# power_PROTECTION.net
KiCad netlist of a schematic drawn in Altium Designer
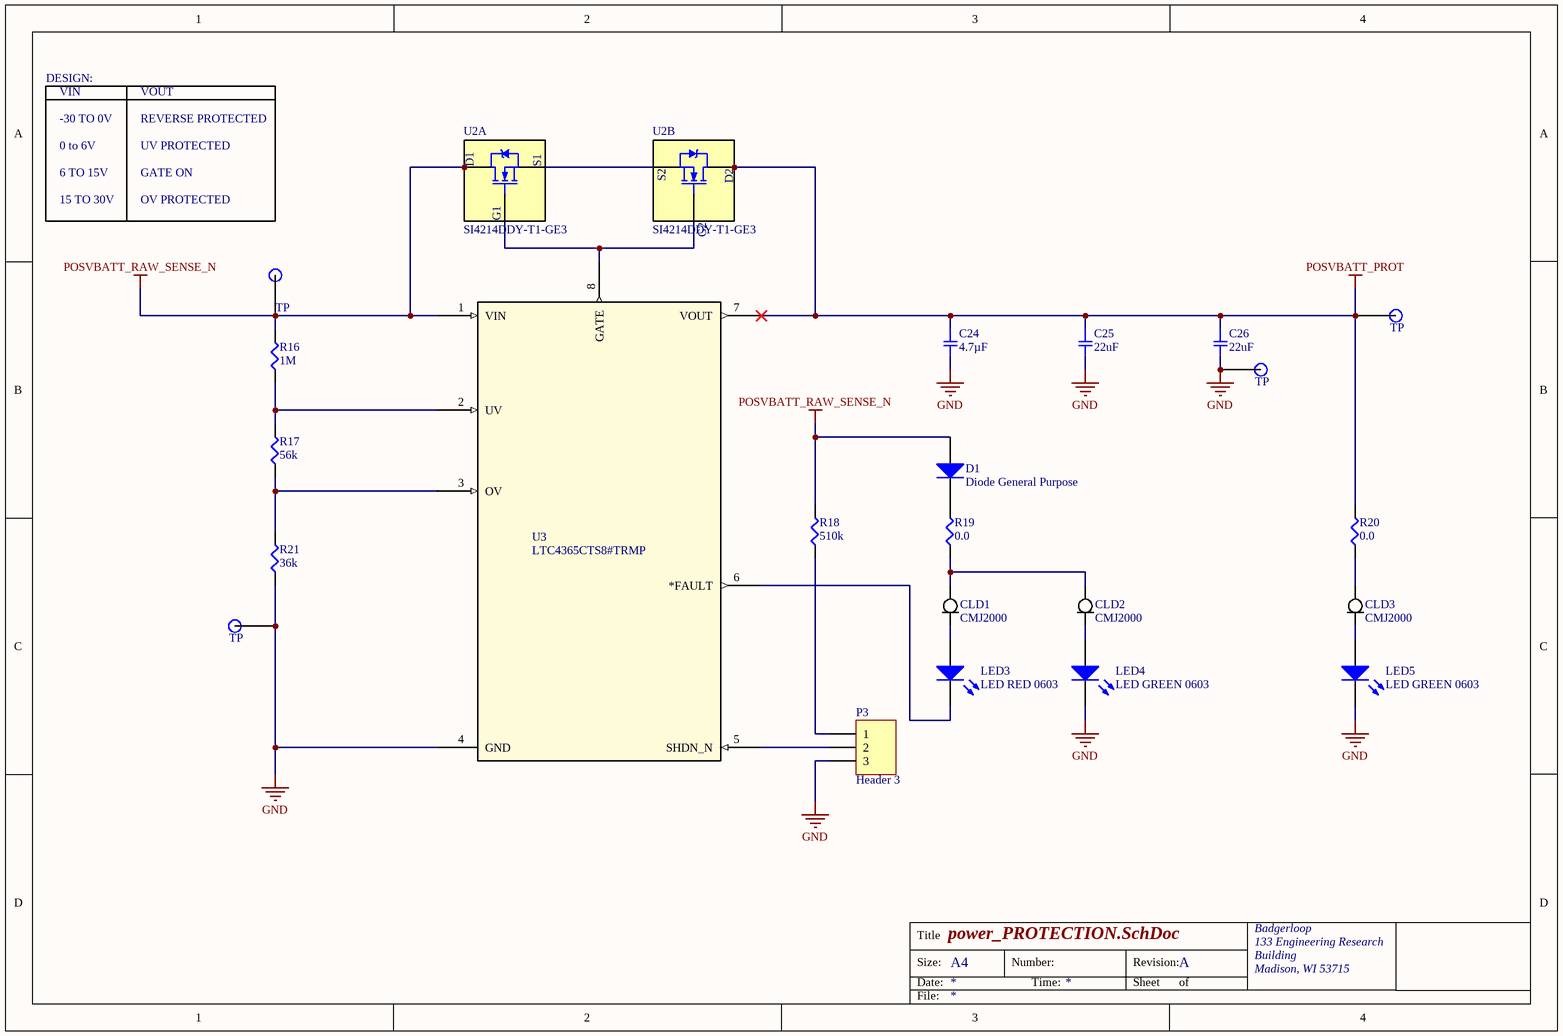
[diagram p0: power_PROTECTION.SchDoc]

(export (version "E")
  (design (tool "Eeschema 10.0.6"))
  (components
    (comp (ref "C24")
      (value "4.7µF")
      (footprint "SMD-0805C")
      (description "CAP CER 4.7UF 50V X5R 0805")
      (fields
        (field (name "DIGI-KEY PART NUMBER") "490-10751-1-ND")
        (field (name "PART NUMBER") "GRM21BR61H475KE51L")
      )
      (libsource (lib "capacitor") (part "GRM21BR61H475KE51L"))
    )
    (comp (ref "C25")
      (value "22uF")
      (footprint "SMD-0805C")
      (description "CAP CER 10000PF 250V X7T 0805")
      (fields
        (field (name "DIGI-KEY PART NUMBER") "445-11527-1-ND")
        (field (name "PART NUMBER") "C2012JB1V226M125AC")
      )
      (libsource (lib "capacitor") (part "GC321AD72E103KX01D"))
    )
    (comp (ref "C26")
      (value "22uF")
      (footprint "SMD-0805C")
      (description "CAP CER 10000PF 250V X7T 0805")
      (fields
        (field (name "DIGI-KEY PART NUMBER") "445-11527-1-ND")
        (field (name "PART NUMBER") "C2012JB1V226M125AC")
      )
      (libsource (lib "capacitor") (part "GC321AD72E103KX01D"))
    )
    (comp (ref "CLD1")
      (value "CMJ2000")
      (footprint "SODFL350X80-2N")
      (description "DIODE CURRENT LIMITING SINGLE SM")
      (fields (field (name "MANUFACTURER") "Central Semiconductor Corp"))
      (libsource (lib "misc") (part "DIODE Current Limiting Single SM"))
    )
    (comp (ref "CLD2")
      (value "CMJ2000")
      (footprint "SODFL350X80-2N")
      (description "DIODE CURRENT LIMITING SINGLE SM")
      (fields (field (name "MANUFACTURER") "Central Semiconductor Corp"))
      (libsource (lib "misc") (part "DIODE Current Limiting Single SM"))
    )
    (comp (ref "CLD3")
      (value "CMJ2000")
      (footprint "SODFL350X80-2N")
      (description "DIODE CURRENT LIMITING SINGLE SM")
      (fields (field (name "MANUFACTURER") "Central Semiconductor Corp"))
      (libsource (lib "misc") (part "DIODE Current Limiting Single SM"))
    )
    (comp (ref "D1")
      (value "Diode General Purpose")
      (footprint "Diode General Purpose")
      (description "DIODE GEN PURP 100V 150MA SOD123")
      (fields (field (name "MANUFACTURER") "Micro Commercial Co"))
      (libsource (lib "misc") (part "Diode General Purpose"))
    )
    (comp (ref "LED3")
      (value "LED RED 0603")
      (footprint "LED 0603 RED")
      (description "Red 631nm LED Indication - Discrete 2V 0603 (1608 Metric)")
      (fields (field (name "MANUFACTURER") "Lite-On Inc."))
      (libsource (lib "misc") (part "LED RED 0603"))
    )
    (comp (ref "LED4")
      (value "LED GREEN 0603")
      (footprint "LED 0603 GREEN")
      (fields (field (name "MANUFACTURER") "Lite-On Inc."))
      (libsource (lib "misc") (part "LED GREEN 0603"))
    )
    (comp (ref "LED5")
      (value "LED GREEN 0603")
      (footprint "LED 0603 GREEN")
      (fields (field (name "MANUFACTURER") "Lite-On Inc."))
      (libsource (lib "misc") (part "LED GREEN 0603"))
    )
    (comp (ref "P3")
      (value "Header 3")
      (footprint "Pin Header 1x3 TH Pitch 2.54mm")
      (description "Header, 3-Pin")
      (fields (field (name "PUBLISHER") "Altium Limited"))
      (libsource (lib "connector") (part "Header 3"))
    )
    (comp (ref "R16")
      (value "1M")
      (footprint "SMD-0402-RES")
      (description "RES SMD 1M OHM 5% 1/10W 0402")
      (fields (field (name "PART NUMBER") "ERJ-2GEJ105X") (field (name "DIGI-KEY PART NUMBER") "P1.0MJCT-ND"))
      (libsource (lib "resistor") (part "ERJ-2GEJ105X"))
    )
    (comp (ref "R17")
      (value "56k")
      (footprint "SMD-0402-RES")
      (description "RES SMD 56K OHM 5% 1/10W 0402")
      (fields (field (name "PART NUMBER") "ERJ-2GEJ563X") (field (name "DIGI-KEY PART NUMBER") "P56KJCT-ND"))
      (libsource (lib "resistor") (part "ERJ-2GEJ563X"))
    )
    (comp (ref "R18")
      (value "510k")
      (footprint "SMD-0402-RES")
      (description "RES SMD 510K OHM 5% 1/10W 0402")
      (fields (field (name "PART NUMBER") "ERJ-2GEJ514X") (field (name "DIGI-KEY PART NUMBER") "P510KJCT-ND"))
      (libsource (lib "resistor") (part "ERJ-2GEJ514X"))
    )
    (comp (ref "R19")
      (value "0.0")
      (footprint "SMD-0402-RES")
      (description "RES SMD 0.0OHM JUMPER 1/10W 0402")
      (fields (field (name "PART NUMBER") "ERJ-2GE0R00X") (field (name "DIGI-KEY PART NUMBER") "P0.0JCT-ND"))
      (libsource (lib "resistor") (part "ERJ-2GE0R00X"))
    )
    (comp (ref "R20")
      (value "0.0")
      (footprint "SMD-0402-RES")
      (description "RES SMD 0.0OHM JUMPER 1/10W 0402")
      (fields (field (name "PART NUMBER") "ERJ-2GE0R00X") (field (name "DIGI-KEY PART NUMBER") "P0.0JCT-ND"))
      (libsource (lib "resistor") (part "ERJ-2GE0R00X"))
    )
    (comp (ref "R21")
      (value "36k")
      (footprint "SMD-0402-RES")
      (description "RES SMD 36K OHM 1% 1/10W 0402")
      (fields
        (field (name "PART NUMBER") "ERJ-2RKF3602X")
        (field (name "DIGI-KEY PART NUMBER") "P36.0KLCT-ND")
      )
      (libsource (lib "resistor") (part "ERJ-2RKF3602X"))
    )
    (comp (ref "TP9") (value "TP") (footprint "Test Point") (libsource (lib "misc") (part "TP")))
    (comp (ref "TP10") (value "TP") (footprint "Test Point") (libsource (lib "misc") (part "TP")))
    (comp (ref "TP11") (value "TP") (footprint "Test Point") (libsource (lib "misc") (part "TP")))
    (comp (ref "TP13") (value "TP") (footprint "Test Point") (libsource (lib "misc") (part "TP")))
    (comp (ref "U2")
      (value "SI4214DDY-T1-GE3")
      (footprint "SOIC-8_SI-L")
      (description "Mosfet Array 2 N-Channel (Dual) 30V 8.5A 3.1W Surface Mount 8-SO")
      (libsource (lib "ic") (part "SI4214DDY-T1-GE3"))
    )
    (comp (ref "U3")
      (value "LTC4365CTS8#TRMP")
      (footprint "TSOT-23_TS8")
      (description "Overvoltage,\r\nUndervoltage and Reverse\r\nSupply Protection Controller")
      (fields (field (name "MANUFACTURER_PART_NUMBER") "LTC4365CTS8#TRMPBF"))
      (libsource (lib "ic") (part "LTC4365CTS8#TRMP"))
    )
  )
  (nets
    (net (code "1") (name "GND") (class "Default")
      (node (ref "C24") (pin "2") (pinfunction "2_2") (pintype "passive"))
      (node (ref "C25") (pin "2") (pinfunction "2_2") (pintype "passive"))
      (node (ref "C26") (pin "2") (pinfunction "2_2") (pintype "passive"))
      (node (ref "LED4") (pin "2") (pinfunction "K_2") (pintype "passive"))
      (node (ref "LED5") (pin "2") (pinfunction "K_2") (pintype "passive"))
      (node (ref "P3") (pin "3") (pinfunction "3_3") (pintype "passive"))
      (node (ref "R21") (pin "1") (pinfunction "1_1") (pintype "passive"))
      (node (ref "TP10") (pin "1") (pinfunction "1_1") (pintype "passive"))
      (node (ref "TP13") (pin "1") (pinfunction "1_1") (pintype "passive"))
      (node (ref "U3") (pin "4") (pinfunction "GND_4") (pintype "power_in"))
    )
    (net (code "2") (name "Net-(CLD1-Pad1)") (class "Default")
      (node (ref "CLD1") (pin "1") (pinfunction "1_1") (pintype "passive"))
      (node (ref "CLD2") (pin "1") (pinfunction "1_1") (pintype "passive"))
      (node (ref "R19") (pin "1") (pinfunction "1_1") (pintype "passive"))
    )
    (net (code "3") (name "Net-(CLD3-Pad1)") (class "Default")
      (node (ref "CLD3") (pin "1") (pinfunction "1_1") (pintype "passive"))
      (node (ref "R20") (pin "1") (pinfunction "1_1") (pintype "passive"))
    )
    (net (code "4") (name "Net-(D1-K)") (class "Default")
      (node (ref "D1") (pin "2") (pinfunction "K_2") (pintype "passive"))
      (node (ref "R19") (pin "2") (pinfunction "2_2") (pintype "passive"))
    )
    (net (code "5") (name "Net-(LED3-A)") (class "Default")
      (node (ref "CLD1") (pin "2") (pinfunction "2_2") (pintype "passive"))
      (node (ref "LED3") (pin "1") (pinfunction "A_1") (pintype "passive"))
    )
    (net (code "6") (name "Net-(LED3-K)") (class "Default")
      (node (ref "LED3") (pin "2") (pinfunction "K_2") (pintype "passive"))
      (node (ref "U3") (pin "6") (pinfunction "*FAULT_6") (pintype "output"))
    )
    (net (code "7") (name "Net-(LED4-A)") (class "Default")
      (node (ref "CLD2") (pin "2") (pinfunction "2_2") (pintype "passive"))
      (node (ref "LED4") (pin "1") (pinfunction "A_1") (pintype "passive"))
    )
    (net (code "8") (name "Net-(LED5-A)") (class "Default")
      (node (ref "CLD3") (pin "2") (pinfunction "2_2") (pintype "passive"))
      (node (ref "LED5") (pin "1") (pinfunction "A_1") (pintype "passive"))
    )
    (net (code "9") (name "Net-(P3-Pad1)") (class "Default")
      (node (ref "P3") (pin "1") (pinfunction "1_1") (pintype "passive"))
      (node (ref "R18") (pin "1") (pinfunction "1_1") (pintype "passive"))
    )
    (net (code "10") (name "Net-(U2A-G1)") (class "Default")
      (node (ref "U2") (pin "2") (pinfunction "G1_2") (pintype "passive"))
      (node (ref "U2") (pin "4") (pinfunction "G2_4") (pintype "passive"))
      (node (ref "U3") (pin "8") (pinfunction "GATE_8") (pintype "output"))
    )
    (net (code "11") (name "Net-(U2A-S1)") (class "Default")
      (node (ref "U2") (pin "1") (pinfunction "S1_1") (pintype "passive"))
      (node (ref "U2") (pin "3") (pinfunction "S2_3") (pintype "passive"))
    )
    (net (code "12") (name "Net-(U3-OV)") (class "Default")
      (node (ref "R17") (pin "1") (pinfunction "1_1") (pintype "passive"))
      (node (ref "R21") (pin "2") (pinfunction "2_2") (pintype "passive"))
      (node (ref "U3") (pin "3") (pinfunction "OV_3") (pintype "input"))
    )
    (net (code "13") (name "Net-(U3-SHDN_N)") (class "Default")
      (node (ref "P3") (pin "2") (pinfunction "2_2") (pintype "passive"))
      (node (ref "U3") (pin "5") (pinfunction "SHDN_N_5") (pintype "input"))
    )
    (net (code "14") (name "Net-(U3-UV)") (class "Default")
      (node (ref "R16") (pin "1") (pinfunction "1_1") (pintype "passive"))
      (node (ref "R17") (pin "2") (pinfunction "2_2") (pintype "passive"))
      (node (ref "U3") (pin "2") (pinfunction "UV_2") (pintype "input"))
    )
    (net (code "15") (name "POSVBATT_PROT") (class "Default")
      (node (ref "C24") (pin "1") (pinfunction "1_1") (pintype "passive"))
      (node (ref "C25") (pin "1") (pinfunction "1_1") (pintype "passive"))
      (node (ref "C26") (pin "1") (pinfunction "1_1") (pintype "passive"))
      (node (ref "R20") (pin "2") (pinfunction "2_2") (pintype "passive"))
      (node (ref "TP11") (pin "1") (pinfunction "1_1") (pintype "passive"))
      (node (ref "U2") (pin "5") (pinfunction "D2_5") (pintype "passive"))
      (node (ref "U2") (pin "6") (pinfunction "D2_6") (pintype "passive"))
      (node (ref "U3") (pin "7") (pinfunction "VOUT_7") (pintype "output"))
    )
    (net (code "16") (name "POSVBATT_RAW_SENSE_N") (class "Default")
      (node (ref "D1") (pin "1") (pinfunction "A_1") (pintype "passive"))
      (node (ref "R16") (pin "2") (pinfunction "2_2") (pintype "passive"))
      (node (ref "R18") (pin "2") (pinfunction "2_2") (pintype "passive"))
      (node (ref "TP9") (pin "1") (pinfunction "1_1") (pintype "passive"))
      (node (ref "U2") (pin "7") (pinfunction "D1_7") (pintype "passive"))
      (node (ref "U2") (pin "8") (pinfunction "D1_8") (pintype "passive"))
      (node (ref "U3") (pin "1") (pinfunction "VIN_1") (pintype "input"))
    )
  )
)
